# EMG_connectors_and_filters_CH_5_8.net
KiCad netlist of a schematic drawn in Altium Designer
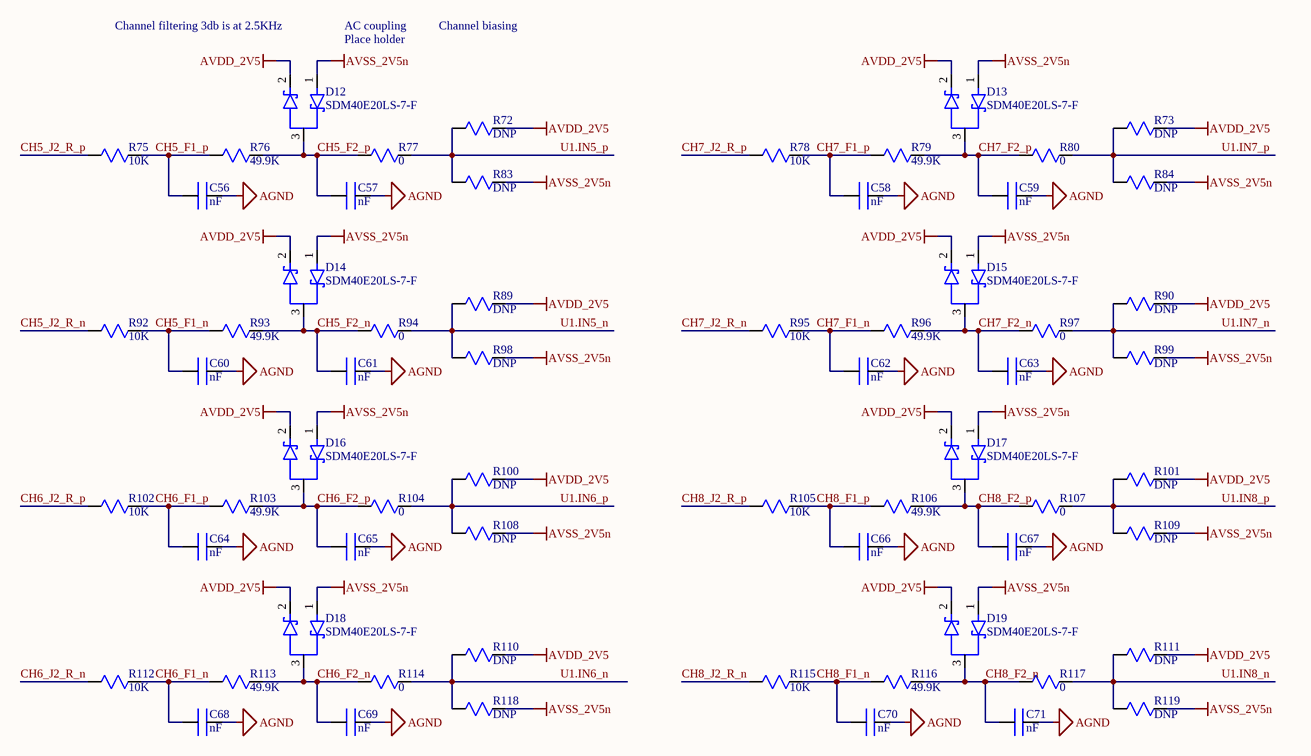
[diagram p0: EMG_connectors_and_filters_CH_5_8.SchDoc]

(export (version "E")
  (design (tool "Eeschema 10.0.6"))
  (components
    (comp (ref "C56")
      (value "nF")
      (footprint "0402")
      (description "CAP CER 1000PF 50V X7R 0402")
      (fields (field (name "MFG") "Samsung"))
      (libsource (lib "Myomo_SCH_Library") (part "C_0402_CER_1nF_50V_X7R"))
    )
    (comp (ref "C57")
      (value "nF")
      (footprint "0402")
      (description "CAP CER 1000PF 50V X7R 0402")
      (fields (field (name "MFG") "Samsung"))
      (libsource (lib "Myomo_SCH_Library") (part "C_0402_CER_1nF_50V_X7R"))
    )
    (comp (ref "C58")
      (value "nF")
      (footprint "0402")
      (description "CAP CER 1000PF 50V X7R 0402")
      (fields (field (name "MFG") "Samsung"))
      (libsource (lib "Myomo_SCH_Library") (part "C_0402_CER_1nF_50V_X7R"))
    )
    (comp (ref "C59")
      (value "nF")
      (footprint "0402")
      (description "CAP CER 1000PF 50V X7R 0402")
      (fields (field (name "MFG") "Samsung"))
      (libsource (lib "Myomo_SCH_Library") (part "C_0402_CER_1nF_50V_X7R"))
    )
    (comp (ref "C60")
      (value "nF")
      (footprint "0402")
      (description "CAP CER 1000PF 50V X7R 0402")
      (fields (field (name "MFG") "Samsung"))
      (libsource (lib "Myomo_SCH_Library") (part "C_0402_CER_1nF_50V_X7R"))
    )
    (comp (ref "C61")
      (value "nF")
      (footprint "0402")
      (description "CAP CER 1000PF 50V X7R 0402")
      (fields (field (name "MFG") "Samsung"))
      (libsource (lib "Myomo_SCH_Library") (part "C_0402_CER_1nF_50V_X7R"))
    )
    (comp (ref "C62")
      (value "nF")
      (footprint "0402")
      (description "CAP CER 1000PF 50V X7R 0402")
      (fields (field (name "MFG") "Samsung"))
      (libsource (lib "Myomo_SCH_Library") (part "C_0402_CER_1nF_50V_X7R"))
    )
    (comp (ref "C63")
      (value "nF")
      (footprint "0402")
      (description "CAP CER 1000PF 50V X7R 0402")
      (fields (field (name "MFG") "Samsung"))
      (libsource (lib "Myomo_SCH_Library") (part "C_0402_CER_1nF_50V_X7R"))
    )
    (comp (ref "C64")
      (value "nF")
      (footprint "0402")
      (description "CAP CER 1000PF 50V X7R 0402")
      (fields (field (name "MFG") "Samsung"))
      (libsource (lib "Myomo_SCH_Library") (part "C_0402_CER_1nF_50V_X7R"))
    )
    (comp (ref "C65")
      (value "nF")
      (footprint "0402")
      (description "CAP CER 1000PF 50V X7R 0402")
      (fields (field (name "MFG") "Samsung"))
      (libsource (lib "Myomo_SCH_Library") (part "C_0402_CER_1nF_50V_X7R"))
    )
    (comp (ref "C66")
      (value "nF")
      (footprint "0402")
      (description "CAP CER 1000PF 50V X7R 0402")
      (fields (field (name "MFG") "Samsung"))
      (libsource (lib "Myomo_SCH_Library") (part "C_0402_CER_1nF_50V_X7R"))
    )
    (comp (ref "C67")
      (value "nF")
      (footprint "0402")
      (description "CAP CER 1000PF 50V X7R 0402")
      (fields (field (name "MFG") "Samsung"))
      (libsource (lib "Myomo_SCH_Library") (part "C_0402_CER_1nF_50V_X7R"))
    )
    (comp (ref "C68")
      (value "nF")
      (footprint "0402")
      (description "CAP CER 1000PF 50V X7R 0402")
      (fields (field (name "MFG") "Samsung"))
      (libsource (lib "Myomo_SCH_Library") (part "C_0402_CER_1nF_50V_X7R"))
    )
    (comp (ref "C69")
      (value "nF")
      (footprint "0402")
      (description "CAP CER 1000PF 50V X7R 0402")
      (fields (field (name "MFG") "Samsung"))
      (libsource (lib "Myomo_SCH_Library") (part "C_0402_CER_1nF_50V_X7R"))
    )
    (comp (ref "C70")
      (value "nF")
      (footprint "0402")
      (description "CAP CER 1000PF 50V X7R 0402")
      (fields (field (name "MFG") "Samsung"))
      (libsource (lib "Myomo_SCH_Library") (part "C_0402_CER_1nF_50V_X7R"))
    )
    (comp (ref "C71")
      (value "nF")
      (footprint "0402")
      (description "CAP CER 1000PF 50V X7R 0402")
      (fields (field (name "MFG") "Samsung"))
      (libsource (lib "Myomo_SCH_Library") (part "C_0402_CER_1nF_50V_X7R"))
    )
    (comp (ref "D12")
      (value "SDM40E20LS-7-F")
      (footprint "D_SCHOTT_0.31mV_400mA")
      (description "DIODE ARR SCHOTT 20V 400MA SOT23")
      (fields (field (name "MFG") "Diodes Incorporated"))
      (libsource (lib "Myomo_SCH_Library") (part "D_SCHOTT_0.31mV_400mA"))
    )
    (comp (ref "D13")
      (value "SDM40E20LS-7-F")
      (footprint "D_SCHOTT_0.31mV_400mA")
      (description "DIODE ARR SCHOTT 20V 400MA SOT23")
      (fields (field (name "MFG") "Diodes Incorporated"))
      (libsource (lib "Myomo_SCH_Library") (part "D_SCHOTT_0.31mV_400mA"))
    )
    (comp (ref "D14")
      (value "SDM40E20LS-7-F")
      (footprint "D_SCHOTT_0.31mV_400mA")
      (description "DIODE ARR SCHOTT 20V 400MA SOT23")
      (fields (field (name "MFG") "Diodes Incorporated"))
      (libsource (lib "Myomo_SCH_Library") (part "D_SCHOTT_0.31mV_400mA"))
    )
    (comp (ref "D15")
      (value "SDM40E20LS-7-F")
      (footprint "D_SCHOTT_0.31mV_400mA")
      (description "DIODE ARR SCHOTT 20V 400MA SOT23")
      (fields (field (name "MFG") "Diodes Incorporated"))
      (libsource (lib "Myomo_SCH_Library") (part "D_SCHOTT_0.31mV_400mA"))
    )
    (comp (ref "D16")
      (value "SDM40E20LS-7-F")
      (footprint "D_SCHOTT_0.31mV_400mA")
      (description "DIODE ARR SCHOTT 20V 400MA SOT23")
      (fields (field (name "MFG") "Diodes Incorporated"))
      (libsource (lib "Myomo_SCH_Library") (part "D_SCHOTT_0.31mV_400mA"))
    )
    (comp (ref "D17")
      (value "SDM40E20LS-7-F")
      (footprint "D_SCHOTT_0.31mV_400mA")
      (description "DIODE ARR SCHOTT 20V 400MA SOT23")
      (fields (field (name "MFG") "Diodes Incorporated"))
      (libsource (lib "Myomo_SCH_Library") (part "D_SCHOTT_0.31mV_400mA"))
    )
    (comp (ref "D18")
      (value "SDM40E20LS-7-F")
      (footprint "D_SCHOTT_0.31mV_400mA")
      (description "DIODE ARR SCHOTT 20V 400MA SOT23")
      (fields (field (name "MFG") "Diodes Incorporated"))
      (libsource (lib "Myomo_SCH_Library") (part "D_SCHOTT_0.31mV_400mA"))
    )
    (comp (ref "D19")
      (value "SDM40E20LS-7-F")
      (footprint "D_SCHOTT_0.31mV_400mA")
      (description "DIODE ARR SCHOTT 20V 400MA SOT23")
      (fields (field (name "MFG") "Diodes Incorporated"))
      (libsource (lib "Myomo_SCH_Library") (part "D_SCHOTT_0.31mV_400mA"))
    )
    (comp (ref "R72")
      (value "DNP")
      (footprint "0402")
      (description "RES 0402 DNP")
      (libsource (lib "Myomo_SCH_Library") (part "R_0402_DNP"))
    )
    (comp (ref "R73")
      (value "DNP")
      (footprint "0402")
      (description "RES 0402 DNP")
      (libsource (lib "Myomo_SCH_Library") (part "R_0402_DNP"))
    )
    (comp (ref "R75")
      (value "10K")
      (footprint "0402")
      (description "RES SMD 10K OHM 1% 1/10W 0402")
      (fields (field (name "MFG") "Panasonic"))
      (libsource (lib "Myomo_SCH_Library") (part "R_0402_10K_1%_1/10W"))
    )
    (comp (ref "R76")
      (value "49.9K")
      (footprint "0402")
      (description "RES SMD 49.9 OHM 1% 1/10W 0402")
      (fields (field (name "MFG") "Panasonic"))
      (libsource (lib "Myomo_SCH_Library") (part "R_0402_49.9K_1%_1/10W"))
    )
    (comp (ref "R77")
      (value "0")
      (footprint "0402")
      (description "RES 0 OHM JUMPER 1/10W 0402")
      (fields (field (name "MFG") "YAGEO"))
      (libsource (lib "Myomo_SCH_Library") (part "R_0402_0"))
    )
    (comp (ref "R78")
      (value "10K")
      (footprint "0402")
      (description "RES SMD 10K OHM 1% 1/10W 0402")
      (fields (field (name "MFG") "Panasonic"))
      (libsource (lib "Myomo_SCH_Library") (part "R_0402_10K_1%_1/10W"))
    )
    (comp (ref "R79")
      (value "49.9K")
      (footprint "0402")
      (description "RES SMD 49.9 OHM 1% 1/10W 0402")
      (fields (field (name "MFG") "Panasonic"))
      (libsource (lib "Myomo_SCH_Library") (part "R_0402_49.9K_1%_1/10W"))
    )
    (comp (ref "R80")
      (value "0")
      (footprint "0402")
      (description "RES 0 OHM JUMPER 1/10W 0402")
      (fields (field (name "MFG") "YAGEO"))
      (libsource (lib "Myomo_SCH_Library") (part "R_0402_0"))
    )
    (comp (ref "R83")
      (value "DNP")
      (footprint "0402")
      (description "RES 0402 DNP")
      (libsource (lib "Myomo_SCH_Library") (part "R_0402_DNP"))
    )
    (comp (ref "R84")
      (value "DNP")
      (footprint "0402")
      (description "RES 0402 DNP")
      (libsource (lib "Myomo_SCH_Library") (part "R_0402_DNP"))
    )
    (comp (ref "R89")
      (value "DNP")
      (footprint "0402")
      (description "RES 0402 DNP")
      (libsource (lib "Myomo_SCH_Library") (part "R_0402_DNP"))
    )
    (comp (ref "R90")
      (value "DNP")
      (footprint "0402")
      (description "RES 0402 DNP")
      (libsource (lib "Myomo_SCH_Library") (part "R_0402_DNP"))
    )
    (comp (ref "R92")
      (value "10K")
      (footprint "0402")
      (description "RES SMD 10K OHM 1% 1/10W 0402")
      (fields (field (name "MFG") "Panasonic"))
      (libsource (lib "Myomo_SCH_Library") (part "R_0402_10K_1%_1/10W"))
    )
    (comp (ref "R93")
      (value "49.9K")
      (footprint "0402")
      (description "RES SMD 49.9 OHM 1% 1/10W 0402")
      (fields (field (name "MFG") "Panasonic"))
      (libsource (lib "Myomo_SCH_Library") (part "R_0402_49.9K_1%_1/10W"))
    )
    (comp (ref "R94")
      (value "0")
      (footprint "0402")
      (description "RES 0 OHM JUMPER 1/10W 0402")
      (fields (field (name "MFG") "YAGEO"))
      (libsource (lib "Myomo_SCH_Library") (part "R_0402_0"))
    )
    (comp (ref "R95")
      (value "10K")
      (footprint "0402")
      (description "RES SMD 10K OHM 1% 1/10W 0402")
      (fields (field (name "MFG") "Panasonic"))
      (libsource (lib "Myomo_SCH_Library") (part "R_0402_10K_1%_1/10W"))
    )
    (comp (ref "R96")
      (value "49.9K")
      (footprint "0402")
      (description "RES SMD 49.9 OHM 1% 1/10W 0402")
      (fields (field (name "MFG") "Panasonic"))
      (libsource (lib "Myomo_SCH_Library") (part "R_0402_49.9K_1%_1/10W"))
    )
    (comp (ref "R97")
      (value "0")
      (footprint "0402")
      (description "RES 0 OHM JUMPER 1/10W 0402")
      (fields (field (name "MFG") "YAGEO"))
      (libsource (lib "Myomo_SCH_Library") (part "R_0402_0"))
    )
    (comp (ref "R98")
      (value "DNP")
      (footprint "0402")
      (description "RES 0402 DNP")
      (libsource (lib "Myomo_SCH_Library") (part "R_0402_DNP"))
    )
    (comp (ref "R99")
      (value "DNP")
      (footprint "0402")
      (description "RES 0402 DNP")
      (libsource (lib "Myomo_SCH_Library") (part "R_0402_DNP"))
    )
    (comp (ref "R100")
      (value "DNP")
      (footprint "0402")
      (description "RES 0402 DNP")
      (libsource (lib "Myomo_SCH_Library") (part "R_0402_DNP"))
    )
    (comp (ref "R101")
      (value "DNP")
      (footprint "0402")
      (description "RES 0402 DNP")
      (libsource (lib "Myomo_SCH_Library") (part "R_0402_DNP"))
    )
    (comp (ref "R102")
      (value "10K")
      (footprint "0402")
      (description "RES SMD 10K OHM 1% 1/10W 0402")
      (fields (field (name "MFG") "Panasonic"))
      (libsource (lib "Myomo_SCH_Library") (part "R_0402_10K_1%_1/10W"))
    )
    (comp (ref "R103")
      (value "49.9K")
      (footprint "0402")
      (description "RES SMD 49.9 OHM 1% 1/10W 0402")
      (fields (field (name "MFG") "Panasonic"))
      (libsource (lib "Myomo_SCH_Library") (part "R_0402_49.9K_1%_1/10W"))
    )
    (comp (ref "R104")
      (value "0")
      (footprint "0402")
      (description "RES 0 OHM JUMPER 1/10W 0402")
      (fields (field (name "MFG") "YAGEO"))
      (libsource (lib "Myomo_SCH_Library") (part "R_0402_0"))
    )
    (comp (ref "R105")
      (value "10K")
      (footprint "0402")
      (description "RES SMD 10K OHM 1% 1/10W 0402")
      (fields (field (name "MFG") "Panasonic"))
      (libsource (lib "Myomo_SCH_Library") (part "R_0402_10K_1%_1/10W"))
    )
    (comp (ref "R106")
      (value "49.9K")
      (footprint "0402")
      (description "RES SMD 49.9 OHM 1% 1/10W 0402")
      (fields (field (name "MFG") "Panasonic"))
      (libsource (lib "Myomo_SCH_Library") (part "R_0402_49.9K_1%_1/10W"))
    )
    (comp (ref "R107")
      (value "0")
      (footprint "0402")
      (description "RES 0 OHM JUMPER 1/10W 0402")
      (fields (field (name "MFG") "YAGEO"))
      (libsource (lib "Myomo_SCH_Library") (part "R_0402_0"))
    )
    (comp (ref "R108")
      (value "DNP")
      (footprint "0402")
      (description "RES 0402 DNP")
      (libsource (lib "Myomo_SCH_Library") (part "R_0402_DNP"))
    )
    (comp (ref "R109")
      (value "DNP")
      (footprint "0402")
      (description "RES 0402 DNP")
      (libsource (lib "Myomo_SCH_Library") (part "R_0402_DNP"))
    )
    (comp (ref "R110")
      (value "DNP")
      (footprint "0402")
      (description "RES 0402 DNP")
      (libsource (lib "Myomo_SCH_Library") (part "R_0402_DNP"))
    )
    (comp (ref "R111")
      (value "DNP")
      (footprint "0402")
      (description "RES 0402 DNP")
      (libsource (lib "Myomo_SCH_Library") (part "R_0402_DNP"))
    )
    (comp (ref "R112")
      (value "10K")
      (footprint "0402")
      (description "RES SMD 10K OHM 1% 1/10W 0402")
      (fields (field (name "MFG") "Panasonic"))
      (libsource (lib "Myomo_SCH_Library") (part "R_0402_10K_1%_1/10W"))
    )
    (comp (ref "R113")
      (value "49.9K")
      (footprint "0402")
      (description "RES SMD 49.9 OHM 1% 1/10W 0402")
      (fields (field (name "MFG") "Panasonic"))
      (libsource (lib "Myomo_SCH_Library") (part "R_0402_49.9K_1%_1/10W"))
    )
    (comp (ref "R114")
      (value "0")
      (footprint "0402")
      (description "RES 0 OHM JUMPER 1/10W 0402")
      (fields (field (name "MFG") "YAGEO"))
      (libsource (lib "Myomo_SCH_Library") (part "R_0402_0"))
    )
    (comp (ref "R115")
      (value "10K")
      (footprint "0402")
      (description "RES SMD 10K OHM 1% 1/10W 0402")
      (fields (field (name "MFG") "Panasonic"))
      (libsource (lib "Myomo_SCH_Library") (part "R_0402_10K_1%_1/10W"))
    )
    (comp (ref "R116")
      (value "49.9K")
      (footprint "0402")
      (description "RES SMD 49.9 OHM 1% 1/10W 0402")
      (fields (field (name "MFG") "Panasonic"))
      (libsource (lib "Myomo_SCH_Library") (part "R_0402_49.9K_1%_1/10W"))
    )
    (comp (ref "R117")
      (value "0")
      (footprint "0402")
      (description "RES 0 OHM JUMPER 1/10W 0402")
      (fields (field (name "MFG") "YAGEO"))
      (libsource (lib "Myomo_SCH_Library") (part "R_0402_0"))
    )
    (comp (ref "R118")
      (value "DNP")
      (footprint "0402")
      (description "RES 0402 DNP")
      (libsource (lib "Myomo_SCH_Library") (part "R_0402_DNP"))
    )
    (comp (ref "R119")
      (value "DNP")
      (footprint "0402")
      (description "RES 0402 DNP")
      (libsource (lib "Myomo_SCH_Library") (part "R_0402_DNP"))
    )
  )
  (nets
    (net (code "1") (name "/CH5_F1_n") (class "Default")
      (node (ref "C60") (pin "1") (pinfunction "1_1") (pintype "passive"))
      (node (ref "R92") (pin "2") (pinfunction "2_2") (pintype "passive"))
      (node (ref "R93") (pin "1") (pinfunction "1_1") (pintype "passive"))
    )
    (net (code "2") (name "/CH5_F1_p") (class "Default")
      (node (ref "C56") (pin "1") (pinfunction "1_1") (pintype "passive"))
      (node (ref "R75") (pin "2") (pinfunction "2_2") (pintype "passive"))
      (node (ref "R76") (pin "1") (pinfunction "1_1") (pintype "passive"))
    )
    (net (code "3") (name "/CH5_F2_n") (class "Default")
      (node (ref "C61") (pin "1") (pinfunction "1_1") (pintype "passive"))
      (node (ref "D14") (pin "3") (pinfunction "K_3") (pintype "passive"))
      (node (ref "R93") (pin "2") (pinfunction "2_2") (pintype "passive"))
      (node (ref "R94") (pin "1") (pinfunction "1_1") (pintype "passive"))
    )
    (net (code "4") (name "/CH5_F2_p") (class "Default")
      (node (ref "C57") (pin "1") (pinfunction "1_1") (pintype "passive"))
      (node (ref "D12") (pin "3") (pinfunction "K_3") (pintype "passive"))
      (node (ref "R76") (pin "2") (pinfunction "2_2") (pintype "passive"))
      (node (ref "R77") (pin "1") (pinfunction "1_1") (pintype "passive"))
    )
    (net (code "5") (name "/CH5_J2_R_n") (class "Default")
      (node (ref "R92") (pin "1") (pinfunction "1_1") (pintype "passive"))
    )
    (net (code "6") (name "/CH5_J2_R_p") (class "Default")
      (node (ref "R75") (pin "1") (pinfunction "1_1") (pintype "passive"))
    )
    (net (code "7") (name "/CH6_F1_n") (class "Default")
      (node (ref "C68") (pin "1") (pinfunction "1_1") (pintype "passive"))
      (node (ref "R112") (pin "2") (pinfunction "2_2") (pintype "passive"))
      (node (ref "R113") (pin "1") (pinfunction "1_1") (pintype "passive"))
    )
    (net (code "8") (name "/CH6_F1_p") (class "Default")
      (node (ref "C64") (pin "1") (pinfunction "1_1") (pintype "passive"))
      (node (ref "R102") (pin "2") (pinfunction "2_2") (pintype "passive"))
      (node (ref "R103") (pin "1") (pinfunction "1_1") (pintype "passive"))
    )
    (net (code "9") (name "/CH6_F2_n") (class "Default")
      (node (ref "C69") (pin "1") (pinfunction "1_1") (pintype "passive"))
      (node (ref "D18") (pin "3") (pinfunction "K_3") (pintype "passive"))
      (node (ref "R113") (pin "2") (pinfunction "2_2") (pintype "passive"))
      (node (ref "R114") (pin "1") (pinfunction "1_1") (pintype "passive"))
    )
    (net (code "10") (name "/CH6_F2_p") (class "Default")
      (node (ref "C65") (pin "1") (pinfunction "1_1") (pintype "passive"))
      (node (ref "D16") (pin "3") (pinfunction "K_3") (pintype "passive"))
      (node (ref "R103") (pin "2") (pinfunction "2_2") (pintype "passive"))
      (node (ref "R104") (pin "1") (pinfunction "1_1") (pintype "passive"))
    )
    (net (code "11") (name "/CH6_J2_R_n") (class "Default")
      (node (ref "R112") (pin "1") (pinfunction "1_1") (pintype "passive"))
    )
    (net (code "12") (name "/CH6_J2_R_p") (class "Default")
      (node (ref "R102") (pin "1") (pinfunction "1_1") (pintype "passive"))
    )
    (net (code "13") (name "/CH7_F1_n") (class "Default")
      (node (ref "C62") (pin "1") (pinfunction "1_1") (pintype "passive"))
      (node (ref "R95") (pin "2") (pinfunction "2_2") (pintype "passive"))
      (node (ref "R96") (pin "1") (pinfunction "1_1") (pintype "passive"))
    )
    (net (code "14") (name "/CH7_F1_p") (class "Default")
      (node (ref "C58") (pin "1") (pinfunction "1_1") (pintype "passive"))
      (node (ref "R78") (pin "2") (pinfunction "2_2") (pintype "passive"))
      (node (ref "R79") (pin "1") (pinfunction "1_1") (pintype "passive"))
    )
    (net (code "15") (name "/CH7_F2_n") (class "Default")
      (node (ref "C63") (pin "1") (pinfunction "1_1") (pintype "passive"))
      (node (ref "D15") (pin "3") (pinfunction "K_3") (pintype "passive"))
      (node (ref "R96") (pin "2") (pinfunction "2_2") (pintype "passive"))
      (node (ref "R97") (pin "1") (pinfunction "1_1") (pintype "passive"))
    )
    (net (code "16") (name "/CH7_F2_p") (class "Default")
      (node (ref "C59") (pin "1") (pinfunction "1_1") (pintype "passive"))
      (node (ref "D13") (pin "3") (pinfunction "K_3") (pintype "passive"))
      (node (ref "R79") (pin "2") (pinfunction "2_2") (pintype "passive"))
      (node (ref "R80") (pin "1") (pinfunction "1_1") (pintype "passive"))
    )
    (net (code "17") (name "/CH7_J2_R_n") (class "Default")
      (node (ref "R95") (pin "1") (pinfunction "1_1") (pintype "passive"))
    )
    (net (code "18") (name "/CH7_J2_R_p") (class "Default")
      (node (ref "R78") (pin "1") (pinfunction "1_1") (pintype "passive"))
    )
    (net (code "19") (name "/CH8_F1_n") (class "Default")
      (node (ref "C70") (pin "1") (pinfunction "1_1") (pintype "passive"))
      (node (ref "R115") (pin "2") (pinfunction "2_2") (pintype "passive"))
      (node (ref "R116") (pin "1") (pinfunction "1_1") (pintype "passive"))
    )
    (net (code "20") (name "/CH8_F1_p") (class "Default")
      (node (ref "C66") (pin "1") (pinfunction "1_1") (pintype "passive"))
      (node (ref "R105") (pin "2") (pinfunction "2_2") (pintype "passive"))
      (node (ref "R106") (pin "1") (pinfunction "1_1") (pintype "passive"))
    )
    (net (code "21") (name "/CH8_F2_n") (class "Default")
      (node (ref "C71") (pin "1") (pinfunction "1_1") (pintype "passive"))
      (node (ref "D19") (pin "3") (pinfunction "K_3") (pintype "passive"))
      (node (ref "R116") (pin "2") (pinfunction "2_2") (pintype "passive"))
      (node (ref "R117") (pin "1") (pinfunction "1_1") (pintype "passive"))
    )
    (net (code "22") (name "/CH8_F2_p") (class "Default")
      (node (ref "C67") (pin "1") (pinfunction "1_1") (pintype "passive"))
      (node (ref "D17") (pin "3") (pinfunction "K_3") (pintype "passive"))
      (node (ref "R106") (pin "2") (pinfunction "2_2") (pintype "passive"))
      (node (ref "R107") (pin "1") (pinfunction "1_1") (pintype "passive"))
    )
    (net (code "23") (name "/CH8_J2_R_n") (class "Default")
      (node (ref "R115") (pin "1") (pinfunction "1_1") (pintype "passive"))
    )
    (net (code "24") (name "/CH8_J2_R_p") (class "Default")
      (node (ref "R105") (pin "1") (pinfunction "1_1") (pintype "passive"))
    )
    (net (code "25") (name "/U1.IN5_n") (class "Default")
      (node (ref "R89") (pin "1") (pinfunction "1_1") (pintype "passive"))
      (node (ref "R94") (pin "2") (pinfunction "2_2") (pintype "passive"))
      (node (ref "R98") (pin "1") (pinfunction "1_1") (pintype "passive"))
    )
    (net (code "26") (name "/U1.IN5_p") (class "Default")
      (node (ref "R72") (pin "1") (pinfunction "1_1") (pintype "passive"))
      (node (ref "R77") (pin "2") (pinfunction "2_2") (pintype "passive"))
      (node (ref "R83") (pin "1") (pinfunction "1_1") (pintype "passive"))
    )
    (net (code "27") (name "/U1.IN6_n") (class "Default")
      (node (ref "R110") (pin "1") (pinfunction "1_1") (pintype "passive"))
      (node (ref "R114") (pin "2") (pinfunction "2_2") (pintype "passive"))
      (node (ref "R118") (pin "1") (pinfunction "1_1") (pintype "passive"))
    )
    (net (code "28") (name "/U1.IN6_p") (class "Default")
      (node (ref "R100") (pin "1") (pinfunction "1_1") (pintype "passive"))
      (node (ref "R104") (pin "2") (pinfunction "2_2") (pintype "passive"))
      (node (ref "R108") (pin "1") (pinfunction "1_1") (pintype "passive"))
    )
    (net (code "29") (name "/U1.IN7_n") (class "Default")
      (node (ref "R90") (pin "1") (pinfunction "1_1") (pintype "passive"))
      (node (ref "R97") (pin "2") (pinfunction "2_2") (pintype "passive"))
      (node (ref "R99") (pin "1") (pinfunction "1_1") (pintype "passive"))
    )
    (net (code "30") (name "/U1.IN7_p") (class "Default")
      (node (ref "R73") (pin "1") (pinfunction "1_1") (pintype "passive"))
      (node (ref "R80") (pin "2") (pinfunction "2_2") (pintype "passive"))
      (node (ref "R84") (pin "1") (pinfunction "1_1") (pintype "passive"))
    )
    (net (code "31") (name "/U1.IN8_n") (class "Default")
      (node (ref "R111") (pin "1") (pinfunction "1_1") (pintype "passive"))
      (node (ref "R117") (pin "2") (pinfunction "2_2") (pintype "passive"))
      (node (ref "R119") (pin "1") (pinfunction "1_1") (pintype "passive"))
    )
    (net (code "32") (name "/U1.IN8_p") (class "Default")
      (node (ref "R101") (pin "1") (pinfunction "1_1") (pintype "passive"))
      (node (ref "R107") (pin "2") (pinfunction "2_2") (pintype "passive"))
      (node (ref "R109") (pin "1") (pinfunction "1_1") (pintype "passive"))
    )
    (net (code "33") (name "AGND") (class "Default")
      (node (ref "C56") (pin "2") (pinfunction "2_2") (pintype "passive"))
      (node (ref "C57") (pin "2") (pinfunction "2_2") (pintype "passive"))
      (node (ref "C58") (pin "2") (pinfunction "2_2") (pintype "passive"))
      (node (ref "C59") (pin "2") (pinfunction "2_2") (pintype "passive"))
      (node (ref "C60") (pin "2") (pinfunction "2_2") (pintype "passive"))
      (node (ref "C61") (pin "2") (pinfunction "2_2") (pintype "passive"))
      (node (ref "C62") (pin "2") (pinfunction "2_2") (pintype "passive"))
      (node (ref "C63") (pin "2") (pinfunction "2_2") (pintype "passive"))
      (node (ref "C64") (pin "2") (pinfunction "2_2") (pintype "passive"))
      (node (ref "C65") (pin "2") (pinfunction "2_2") (pintype "passive"))
      (node (ref "C66") (pin "2") (pinfunction "2_2") (pintype "passive"))
      (node (ref "C67") (pin "2") (pinfunction "2_2") (pintype "passive"))
      (node (ref "C68") (pin "2") (pinfunction "2_2") (pintype "passive"))
      (node (ref "C69") (pin "2") (pinfunction "2_2") (pintype "passive"))
      (node (ref "C70") (pin "2") (pinfunction "2_2") (pintype "passive"))
      (node (ref "C71") (pin "2") (pinfunction "2_2") (pintype "passive"))
    )
    (net (code "34") (name "AVDD_2V5") (class "Default")
      (node (ref "D12") (pin "2") (pinfunction "A2_2") (pintype "passive"))
      (node (ref "D13") (pin "2") (pinfunction "A2_2") (pintype "passive"))
      (node (ref "D14") (pin "2") (pinfunction "A2_2") (pintype "passive"))
      (node (ref "D15") (pin "2") (pinfunction "A2_2") (pintype "passive"))
      (node (ref "D16") (pin "2") (pinfunction "A2_2") (pintype "passive"))
      (node (ref "D17") (pin "2") (pinfunction "A2_2") (pintype "passive"))
      (node (ref "D18") (pin "2") (pinfunction "A2_2") (pintype "passive"))
      (node (ref "D19") (pin "2") (pinfunction "A2_2") (pintype "passive"))
      (node (ref "R100") (pin "2") (pinfunction "2_2") (pintype "passive"))
      (node (ref "R101") (pin "2") (pinfunction "2_2") (pintype "passive"))
      (node (ref "R110") (pin "2") (pinfunction "2_2") (pintype "passive"))
      (node (ref "R111") (pin "2") (pinfunction "2_2") (pintype "passive"))
      (node (ref "R72") (pin "2") (pinfunction "2_2") (pintype "passive"))
      (node (ref "R73") (pin "2") (pinfunction "2_2") (pintype "passive"))
      (node (ref "R89") (pin "2") (pinfunction "2_2") (pintype "passive"))
      (node (ref "R90") (pin "2") (pinfunction "2_2") (pintype "passive"))
    )
    (net (code "35") (name "AVSS_2V5n") (class "Default")
      (node (ref "D12") (pin "1") (pinfunction "A1_1") (pintype "passive"))
      (node (ref "D13") (pin "1") (pinfunction "A1_1") (pintype "passive"))
      (node (ref "D14") (pin "1") (pinfunction "A1_1") (pintype "passive"))
      (node (ref "D15") (pin "1") (pinfunction "A1_1") (pintype "passive"))
      (node (ref "D16") (pin "1") (pinfunction "A1_1") (pintype "passive"))
      (node (ref "D17") (pin "1") (pinfunction "A1_1") (pintype "passive"))
      (node (ref "D18") (pin "1") (pinfunction "A1_1") (pintype "passive"))
      (node (ref "D19") (pin "1") (pinfunction "A1_1") (pintype "passive"))
      (node (ref "R108") (pin "2") (pinfunction "2_2") (pintype "passive"))
      (node (ref "R109") (pin "2") (pinfunction "2_2") (pintype "passive"))
      (node (ref "R118") (pin "2") (pinfunction "2_2") (pintype "passive"))
      (node (ref "R119") (pin "2") (pinfunction "2_2") (pintype "passive"))
      (node (ref "R83") (pin "2") (pinfunction "2_2") (pintype "passive"))
      (node (ref "R84") (pin "2") (pinfunction "2_2") (pintype "passive"))
      (node (ref "R98") (pin "2") (pinfunction "2_2") (pintype "passive"))
      (node (ref "R99") (pin "2") (pinfunction "2_2") (pintype "passive"))
    )
  )
)
